# candle.net
KiCad netlist of a schematic drawn in EAGLE
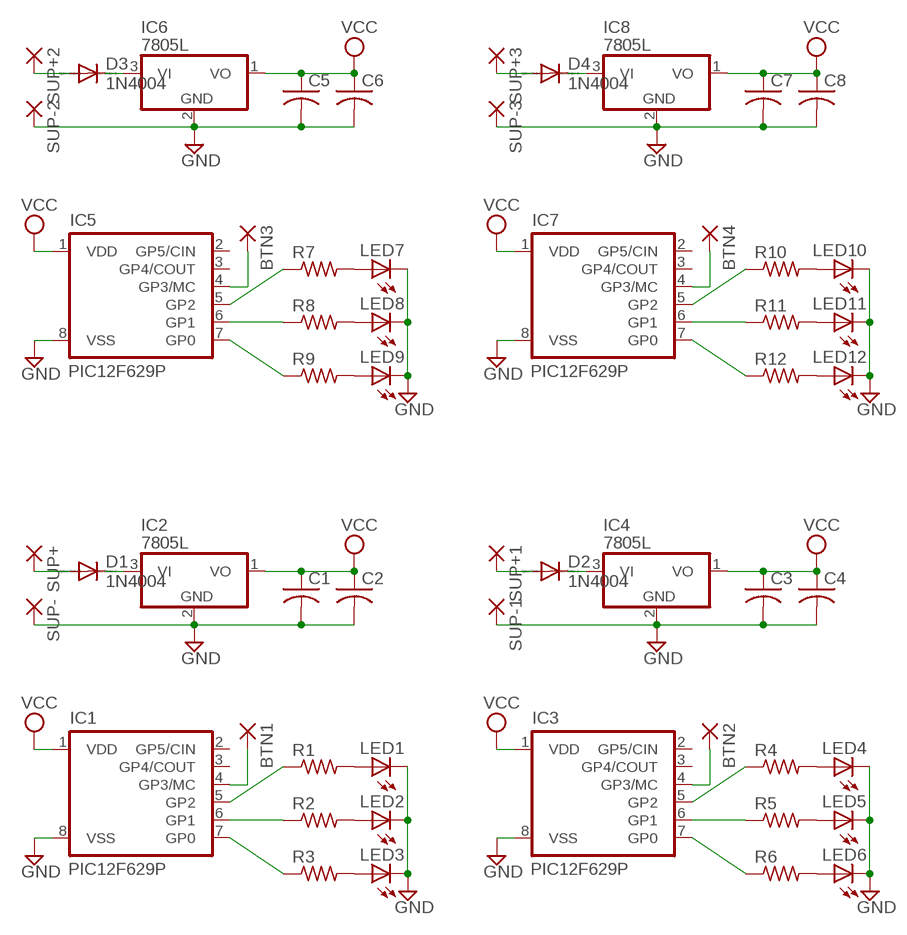
[diagram p0: schematic, sheet 1]

(export (version "E")
  (design (tool "Eeschema 10.0.6"))
  (components
    (comp (ref "BTN1")
      (value "1,6/0,8")
      (footprint "eagle-import:1,6_0,8")
      (libsource (lib "eagle-import") (part "1,6/0,8"))
    )
    (comp (ref "BTN2")
      (value "1,6/0,8")
      (footprint "eagle-import:1,6_0,8")
      (libsource (lib "eagle-import") (part "1,6/0,8"))
    )
    (comp (ref "BTN3")
      (value "1,6/0,8")
      (footprint "eagle-import:1,6_0,8")
      (libsource (lib "eagle-import") (part "1,6/0,8"))
    )
    (comp (ref "BTN4")
      (value "1,6/0,8")
      (footprint "eagle-import:1,6_0,8")
      (libsource (lib "eagle-import") (part "1,6/0,8"))
    )
    (comp (ref "C1")
      (value "C-US025-025X050")
      (footprint "eagle-import:C025-025X050")
      (libsource (lib "eagle-import") (part "C-US025-025X050"))
    )
    (comp (ref "C2")
      (value "C-US025-025X050")
      (footprint "eagle-import:C025-025X050")
      (libsource (lib "eagle-import") (part "C-US025-025X050"))
    )
    (comp (ref "C3")
      (value "C-US025-025X050")
      (footprint "eagle-import:C025-025X050")
      (libsource (lib "eagle-import") (part "C-US025-025X050"))
    )
    (comp (ref "C4")
      (value "C-US025-025X050")
      (footprint "eagle-import:C025-025X050")
      (libsource (lib "eagle-import") (part "C-US025-025X050"))
    )
    (comp (ref "C5")
      (value "C-US025-025X050")
      (footprint "eagle-import:C025-025X050")
      (libsource (lib "eagle-import") (part "C-US025-025X050"))
    )
    (comp (ref "C6")
      (value "C-US025-025X050")
      (footprint "eagle-import:C025-025X050")
      (libsource (lib "eagle-import") (part "C-US025-025X050"))
    )
    (comp (ref "C7")
      (value "C-US025-025X050")
      (footprint "eagle-import:C025-025X050")
      (libsource (lib "eagle-import") (part "C-US025-025X050"))
    )
    (comp (ref "C8")
      (value "C-US025-025X050")
      (footprint "eagle-import:C025-025X050")
      (libsource (lib "eagle-import") (part "C-US025-025X050"))
    )
    (comp (ref "D1")
      (value "1N4004")
      (footprint "eagle-import:DO41-10")
      (libsource (lib "eagle-import") (part "1N4004"))
    )
    (comp (ref "D2")
      (value "1N4004")
      (footprint "eagle-import:DO41-10")
      (libsource (lib "eagle-import") (part "1N4004"))
    )
    (comp (ref "D3")
      (value "1N4004")
      (footprint "eagle-import:DO41-10")
      (libsource (lib "eagle-import") (part "1N4004"))
    )
    (comp (ref "D4")
      (value "1N4004")
      (footprint "eagle-import:DO41-10")
      (libsource (lib "eagle-import") (part "1N4004"))
    )
    (comp (ref "IC1")
      (value "PIC12F629P")
      (footprint "eagle-import:DIL8")
      (fields (field (name "MF") "MICROCHIP") (field (name "MPN") "PIC12C671-10/P"))
      (libsource (lib "eagle-import") (part "PIC12C?P671"))
    )
    (comp (ref "IC2")
      (value "7805L")
      (footprint "eagle-import:TO92")
      (libsource (lib "eagle-import") (part "78L05"))
    )
    (comp (ref "IC3")
      (value "PIC12F629P")
      (footprint "eagle-import:DIL8")
      (fields (field (name "MF") "MICROCHIP") (field (name "MPN") "PIC12C671-10/P"))
      (libsource (lib "eagle-import") (part "PIC12C?P671"))
    )
    (comp (ref "IC4")
      (value "7805L")
      (footprint "eagle-import:TO92")
      (libsource (lib "eagle-import") (part "78L05"))
    )
    (comp (ref "IC5")
      (value "PIC12F629P")
      (footprint "eagle-import:DIL8")
      (fields (field (name "MF") "MICROCHIP") (field (name "MPN") "PIC12C671-10/P"))
      (libsource (lib "eagle-import") (part "PIC12C?P671"))
    )
    (comp (ref "IC6")
      (value "7805L")
      (footprint "eagle-import:TO92")
      (libsource (lib "eagle-import") (part "78L05"))
    )
    (comp (ref "IC7")
      (value "PIC12F629P")
      (footprint "eagle-import:DIL8")
      (fields (field (name "MF") "MICROCHIP") (field (name "MPN") "PIC12C671-10/P"))
      (libsource (lib "eagle-import") (part "PIC12C?P671"))
    )
    (comp (ref "IC8")
      (value "7805L")
      (footprint "eagle-import:TO92")
      (libsource (lib "eagle-import") (part "78L05"))
    )
    (comp (ref "LED1")
      (value "LED5MM")
      (footprint "eagle-import:LED5MM")
      (libsource (lib "eagle-import") (part "LED5MM"))
    )
    (comp (ref "LED2")
      (value "LED5MM")
      (footprint "eagle-import:LED5MM")
      (libsource (lib "eagle-import") (part "LED5MM"))
    )
    (comp (ref "LED3")
      (value "LED5MM")
      (footprint "eagle-import:LED5MM")
      (libsource (lib "eagle-import") (part "LED5MM"))
    )
    (comp (ref "LED4")
      (value "LED5MM")
      (footprint "eagle-import:LED5MM")
      (libsource (lib "eagle-import") (part "LED5MM"))
    )
    (comp (ref "LED5")
      (value "LED5MM")
      (footprint "eagle-import:LED5MM")
      (libsource (lib "eagle-import") (part "LED5MM"))
    )
    (comp (ref "LED6")
      (value "LED5MM")
      (footprint "eagle-import:LED5MM")
      (libsource (lib "eagle-import") (part "LED5MM"))
    )
    (comp (ref "LED7")
      (value "LED5MM")
      (footprint "eagle-import:LED5MM")
      (libsource (lib "eagle-import") (part "LED5MM"))
    )
    (comp (ref "LED8")
      (value "LED5MM")
      (footprint "eagle-import:LED5MM")
      (libsource (lib "eagle-import") (part "LED5MM"))
    )
    (comp (ref "LED9")
      (value "LED5MM")
      (footprint "eagle-import:LED5MM")
      (libsource (lib "eagle-import") (part "LED5MM"))
    )
    (comp (ref "LED10")
      (value "LED5MM")
      (footprint "eagle-import:LED5MM")
      (libsource (lib "eagle-import") (part "LED5MM"))
    )
    (comp (ref "LED11")
      (value "LED5MM")
      (footprint "eagle-import:LED5MM")
      (libsource (lib "eagle-import") (part "LED5MM"))
    )
    (comp (ref "LED12")
      (value "LED5MM")
      (footprint "eagle-import:LED5MM")
      (libsource (lib "eagle-import") (part "LED5MM"))
    )
    (comp (ref "R1")
      (value "R-US_0204/7")
      (footprint "eagle-import:0204_7")
      (libsource (lib "eagle-import") (part "R-US_0204/7"))
    )
    (comp (ref "R2")
      (value "R-US_0204/7")
      (footprint "eagle-import:0204_7")
      (libsource (lib "eagle-import") (part "R-US_0204/7"))
    )
    (comp (ref "R3")
      (value "R-US_0204/7")
      (footprint "eagle-import:0204_7")
      (libsource (lib "eagle-import") (part "R-US_0204/7"))
    )
    (comp (ref "R4")
      (value "R-US_0204/7")
      (footprint "eagle-import:0204_7")
      (libsource (lib "eagle-import") (part "R-US_0204/7"))
    )
    (comp (ref "R5")
      (value "R-US_0204/7")
      (footprint "eagle-import:0204_7")
      (libsource (lib "eagle-import") (part "R-US_0204/7"))
    )
    (comp (ref "R6")
      (value "R-US_0204/7")
      (footprint "eagle-import:0204_7")
      (libsource (lib "eagle-import") (part "R-US_0204/7"))
    )
    (comp (ref "R7")
      (value "R-US_0204/7")
      (footprint "eagle-import:0204_7")
      (libsource (lib "eagle-import") (part "R-US_0204/7"))
    )
    (comp (ref "R8")
      (value "R-US_0204/7")
      (footprint "eagle-import:0204_7")
      (libsource (lib "eagle-import") (part "R-US_0204/7"))
    )
    (comp (ref "R9")
      (value "R-US_0204/7")
      (footprint "eagle-import:0204_7")
      (libsource (lib "eagle-import") (part "R-US_0204/7"))
    )
    (comp (ref "R10")
      (value "R-US_0204/7")
      (footprint "eagle-import:0204_7")
      (libsource (lib "eagle-import") (part "R-US_0204/7"))
    )
    (comp (ref "R11")
      (value "R-US_0204/7")
      (footprint "eagle-import:0204_7")
      (libsource (lib "eagle-import") (part "R-US_0204/7"))
    )
    (comp (ref "R12")
      (value "R-US_0204/7")
      (footprint "eagle-import:0204_7")
      (libsource (lib "eagle-import") (part "R-US_0204/7"))
    )
    (comp (ref "SUP+")
      (value "1,6/0,8")
      (footprint "eagle-import:1,6_0,8")
      (libsource (lib "eagle-import") (part "1,6/0,8"))
    )
    (comp (ref "SUP+1")
      (value "1,6/0,8")
      (footprint "eagle-import:1,6_0,8")
      (libsource (lib "eagle-import") (part "1,6/0,8"))
    )
    (comp (ref "SUP+2")
      (value "1,6/0,8")
      (footprint "eagle-import:1,6_0,8")
      (libsource (lib "eagle-import") (part "1,6/0,8"))
    )
    (comp (ref "SUP+3")
      (value "1,6/0,8")
      (footprint "eagle-import:1,6_0,8")
      (libsource (lib "eagle-import") (part "1,6/0,8"))
    )
    (comp (ref "SUP-")
      (value "1,6/0,8")
      (footprint "eagle-import:1,6_0,8")
      (libsource (lib "eagle-import") (part "1,6/0,8"))
    )
    (comp (ref "SUP-1")
      (value "1,6/0,8")
      (footprint "eagle-import:1,6_0,8")
      (libsource (lib "eagle-import") (part "1,6/0,8"))
    )
    (comp (ref "SUP-2")
      (value "1,6/0,8")
      (footprint "eagle-import:1,6_0,8")
      (libsource (lib "eagle-import") (part "1,6/0,8"))
    )
    (comp (ref "SUP-3")
      (value "1,6/0,8")
      (footprint "eagle-import:1,6_0,8")
      (libsource (lib "eagle-import") (part "1,6/0,8"))
    )
  )
  (nets
    (net (code "1") (name "GND") (class "Default")
      (node (ref "C1") (pin "2") (pinfunction "2_2") (pintype "passive"))
      (node (ref "C2") (pin "2") (pinfunction "2_2") (pintype "passive"))
      (node (ref "C3") (pin "2") (pinfunction "2_2") (pintype "passive"))
      (node (ref "C4") (pin "2") (pinfunction "2_2") (pintype "passive"))
      (node (ref "C5") (pin "2") (pinfunction "2_2") (pintype "passive"))
      (node (ref "C6") (pin "2") (pinfunction "2_2") (pintype "passive"))
      (node (ref "C7") (pin "2") (pinfunction "2_2") (pintype "passive"))
      (node (ref "C8") (pin "2") (pinfunction "2_2") (pintype "passive"))
      (node (ref "IC1") (pin "8") (pinfunction "VSS_8") (pintype "power_in"))
      (node (ref "IC2") (pin "2") (pinfunction "GND_2") (pintype "passive"))
      (node (ref "IC3") (pin "8") (pinfunction "VSS_8") (pintype "power_in"))
      (node (ref "IC4") (pin "2") (pinfunction "GND_2") (pintype "passive"))
      (node (ref "IC5") (pin "8") (pinfunction "VSS_8") (pintype "power_in"))
      (node (ref "IC6") (pin "2") (pinfunction "GND_2") (pintype "passive"))
      (node (ref "IC7") (pin "8") (pinfunction "VSS_8") (pintype "power_in"))
      (node (ref "IC8") (pin "2") (pinfunction "GND_2") (pintype "passive"))
      (node (ref "LED1") (pin "K") (pinfunction "C_K") (pintype "passive"))
      (node (ref "LED10") (pin "K") (pinfunction "C_K") (pintype "passive"))
      (node (ref "LED11") (pin "K") (pinfunction "C_K") (pintype "passive"))
      (node (ref "LED12") (pin "K") (pinfunction "C_K") (pintype "passive"))
      (node (ref "LED2") (pin "K") (pinfunction "C_K") (pintype "passive"))
      (node (ref "LED3") (pin "K") (pinfunction "C_K") (pintype "passive"))
      (node (ref "LED4") (pin "K") (pinfunction "C_K") (pintype "passive"))
      (node (ref "LED5") (pin "K") (pinfunction "C_K") (pintype "passive"))
      (node (ref "LED6") (pin "K") (pinfunction "C_K") (pintype "passive"))
      (node (ref "LED7") (pin "K") (pinfunction "C_K") (pintype "passive"))
      (node (ref "LED8") (pin "K") (pinfunction "C_K") (pintype "passive"))
      (node (ref "LED9") (pin "K") (pinfunction "C_K") (pintype "passive"))
      (node (ref "SUP-") (pin "1") (pinfunction "P_1") (pintype "passive"))
      (node (ref "SUP-1") (pin "1") (pinfunction "P_1") (pintype "passive"))
      (node (ref "SUP-2") (pin "1") (pinfunction "P_1") (pintype "passive"))
      (node (ref "SUP-3") (pin "1") (pinfunction "P_1") (pintype "passive"))
    )
    (net (code "2") (name "Net-(BTN1-P)") (class "Default")
      (node (ref "BTN1") (pin "1") (pinfunction "P_1") (pintype "passive"))
      (node (ref "IC1") (pin "4") (pinfunction "GP3/MC_4") (pintype "input"))
    )
    (net (code "3") (name "Net-(BTN2-P)") (class "Default")
      (node (ref "BTN2") (pin "1") (pinfunction "P_1") (pintype "passive"))
      (node (ref "IC3") (pin "4") (pinfunction "GP3/MC_4") (pintype "input"))
    )
    (net (code "4") (name "Net-(BTN3-P)") (class "Default")
      (node (ref "BTN3") (pin "1") (pinfunction "P_1") (pintype "passive"))
      (node (ref "IC5") (pin "4") (pinfunction "GP3/MC_4") (pintype "input"))
    )
    (net (code "5") (name "Net-(BTN4-P)") (class "Default")
      (node (ref "BTN4") (pin "1") (pinfunction "P_1") (pintype "passive"))
      (node (ref "IC7") (pin "4") (pinfunction "GP3/MC_4") (pintype "input"))
    )
    (net (code "6") (name "Net-(IC1-GP0)") (class "Default")
      (node (ref "IC1") (pin "7") (pinfunction "GP0_7") (pintype "bidirectional"))
      (node (ref "R3") (pin "1") (pinfunction "1_1") (pintype "passive"))
    )
    (net (code "7") (name "Net-(IC1-GP1)") (class "Default")
      (node (ref "IC1") (pin "6") (pinfunction "GP1_6") (pintype "bidirectional"))
      (node (ref "R2") (pin "1") (pinfunction "1_1") (pintype "passive"))
    )
    (net (code "8") (name "Net-(IC1-GP2)") (class "Default")
      (node (ref "IC1") (pin "5") (pinfunction "GP2_5") (pintype "bidirectional"))
      (node (ref "R1") (pin "1") (pinfunction "1_1") (pintype "passive"))
    )
    (net (code "9") (name "Net-(IC2-VI)") (class "Default")
      (node (ref "D1") (pin "C") (pinfunction "C_C") (pintype "passive"))
      (node (ref "IC2") (pin "3") (pinfunction "VI_3") (pintype "input"))
    )
    (net (code "10") (name "Net-(IC3-GP0)") (class "Default")
      (node (ref "IC3") (pin "7") (pinfunction "GP0_7") (pintype "bidirectional"))
      (node (ref "R6") (pin "1") (pinfunction "1_1") (pintype "passive"))
    )
    (net (code "11") (name "Net-(IC3-GP1)") (class "Default")
      (node (ref "IC3") (pin "6") (pinfunction "GP1_6") (pintype "bidirectional"))
      (node (ref "R5") (pin "1") (pinfunction "1_1") (pintype "passive"))
    )
    (net (code "12") (name "Net-(IC3-GP2)") (class "Default")
      (node (ref "IC3") (pin "5") (pinfunction "GP2_5") (pintype "bidirectional"))
      (node (ref "R4") (pin "1") (pinfunction "1_1") (pintype "passive"))
    )
    (net (code "13") (name "Net-(IC4-VI)") (class "Default")
      (node (ref "D2") (pin "C") (pinfunction "C_C") (pintype "passive"))
      (node (ref "IC4") (pin "3") (pinfunction "VI_3") (pintype "input"))
    )
    (net (code "14") (name "Net-(IC5-GP0)") (class "Default")
      (node (ref "IC5") (pin "7") (pinfunction "GP0_7") (pintype "bidirectional"))
      (node (ref "R9") (pin "1") (pinfunction "1_1") (pintype "passive"))
    )
    (net (code "15") (name "Net-(IC5-GP1)") (class "Default")
      (node (ref "IC5") (pin "6") (pinfunction "GP1_6") (pintype "bidirectional"))
      (node (ref "R8") (pin "1") (pinfunction "1_1") (pintype "passive"))
    )
    (net (code "16") (name "Net-(IC5-GP2)") (class "Default")
      (node (ref "IC5") (pin "5") (pinfunction "GP2_5") (pintype "bidirectional"))
      (node (ref "R7") (pin "1") (pinfunction "1_1") (pintype "passive"))
    )
    (net (code "17") (name "Net-(IC6-VI)") (class "Default")
      (node (ref "D3") (pin "C") (pinfunction "C_C") (pintype "passive"))
      (node (ref "IC6") (pin "3") (pinfunction "VI_3") (pintype "input"))
    )
    (net (code "18") (name "Net-(IC7-GP0)") (class "Default")
      (node (ref "IC7") (pin "7") (pinfunction "GP0_7") (pintype "bidirectional"))
      (node (ref "R12") (pin "1") (pinfunction "1_1") (pintype "passive"))
    )
    (net (code "19") (name "Net-(IC7-GP1)") (class "Default")
      (node (ref "IC7") (pin "6") (pinfunction "GP1_6") (pintype "bidirectional"))
      (node (ref "R11") (pin "1") (pinfunction "1_1") (pintype "passive"))
    )
    (net (code "20") (name "Net-(IC7-GP2)") (class "Default")
      (node (ref "IC7") (pin "5") (pinfunction "GP2_5") (pintype "bidirectional"))
      (node (ref "R10") (pin "1") (pinfunction "1_1") (pintype "passive"))
    )
    (net (code "21") (name "Net-(IC8-VI)") (class "Default")
      (node (ref "D4") (pin "C") (pinfunction "C_C") (pintype "passive"))
      (node (ref "IC8") (pin "3") (pinfunction "VI_3") (pintype "input"))
    )
    (net (code "22") (name "Net-(LED1-PadA)") (class "Default")
      (node (ref "LED1") (pin "A") (pinfunction "A_A") (pintype "passive"))
      (node (ref "R1") (pin "2") (pinfunction "2_2") (pintype "passive"))
    )
    (net (code "23") (name "Net-(LED2-PadA)") (class "Default")
      (node (ref "LED2") (pin "A") (pinfunction "A_A") (pintype "passive"))
      (node (ref "R2") (pin "2") (pinfunction "2_2") (pintype "passive"))
    )
    (net (code "24") (name "Net-(LED3-PadA)") (class "Default")
      (node (ref "LED3") (pin "A") (pinfunction "A_A") (pintype "passive"))
      (node (ref "R3") (pin "2") (pinfunction "2_2") (pintype "passive"))
    )
    (net (code "25") (name "Net-(LED4-PadA)") (class "Default")
      (node (ref "LED4") (pin "A") (pinfunction "A_A") (pintype "passive"))
      (node (ref "R4") (pin "2") (pinfunction "2_2") (pintype "passive"))
    )
    (net (code "26") (name "Net-(LED5-PadA)") (class "Default")
      (node (ref "LED5") (pin "A") (pinfunction "A_A") (pintype "passive"))
      (node (ref "R5") (pin "2") (pinfunction "2_2") (pintype "passive"))
    )
    (net (code "27") (name "Net-(LED6-PadA)") (class "Default")
      (node (ref "LED6") (pin "A") (pinfunction "A_A") (pintype "passive"))
      (node (ref "R6") (pin "2") (pinfunction "2_2") (pintype "passive"))
    )
    (net (code "28") (name "Net-(LED7-PadA)") (class "Default")
      (node (ref "LED7") (pin "A") (pinfunction "A_A") (pintype "passive"))
      (node (ref "R7") (pin "2") (pinfunction "2_2") (pintype "passive"))
    )
    (net (code "29") (name "Net-(LED8-PadA)") (class "Default")
      (node (ref "LED8") (pin "A") (pinfunction "A_A") (pintype "passive"))
      (node (ref "R8") (pin "2") (pinfunction "2_2") (pintype "passive"))
    )
    (net (code "30") (name "Net-(LED9-PadA)") (class "Default")
      (node (ref "LED9") (pin "A") (pinfunction "A_A") (pintype "passive"))
      (node (ref "R9") (pin "2") (pinfunction "2_2") (pintype "passive"))
    )
    (net (code "31") (name "Net-(LED10-PadA)") (class "Default")
      (node (ref "LED10") (pin "A") (pinfunction "A_A") (pintype "passive"))
      (node (ref "R10") (pin "2") (pinfunction "2_2") (pintype "passive"))
    )
    (net (code "32") (name "Net-(LED11-PadA)") (class "Default")
      (node (ref "LED11") (pin "A") (pinfunction "A_A") (pintype "passive"))
      (node (ref "R11") (pin "2") (pinfunction "2_2") (pintype "passive"))
    )
    (net (code "33") (name "Net-(LED12-PadA)") (class "Default")
      (node (ref "LED12") (pin "A") (pinfunction "A_A") (pintype "passive"))
      (node (ref "R12") (pin "2") (pinfunction "2_2") (pintype "passive"))
    )
    (net (code "34") (name "Net-(SUP+-P)") (class "Default")
      (node (ref "D1") (pin "A") (pinfunction "A_A") (pintype "passive"))
      (node (ref "SUP+") (pin "1") (pinfunction "P_1") (pintype "passive"))
    )
    (net (code "35") (name "Net-(SUP+1-P)") (class "Default")
      (node (ref "D2") (pin "A") (pinfunction "A_A") (pintype "passive"))
      (node (ref "SUP+1") (pin "1") (pinfunction "P_1") (pintype "passive"))
    )
    (net (code "36") (name "Net-(SUP+2-P)") (class "Default")
      (node (ref "D3") (pin "A") (pinfunction "A_A") (pintype "passive"))
      (node (ref "SUP+2") (pin "1") (pinfunction "P_1") (pintype "passive"))
    )
    (net (code "37") (name "Net-(SUP+3-P)") (class "Default")
      (node (ref "D4") (pin "A") (pinfunction "A_A") (pintype "passive"))
      (node (ref "SUP+3") (pin "1") (pinfunction "P_1") (pintype "passive"))
    )
    (net (code "38") (name "VCC") (class "Default")
      (node (ref "C1") (pin "1") (pinfunction "1_1") (pintype "passive"))
      (node (ref "C2") (pin "1") (pinfunction "1_1") (pintype "passive"))
      (node (ref "C3") (pin "1") (pinfunction "1_1") (pintype "passive"))
      (node (ref "C4") (pin "1") (pinfunction "1_1") (pintype "passive"))
      (node (ref "C5") (pin "1") (pinfunction "1_1") (pintype "passive"))
      (node (ref "C6") (pin "1") (pinfunction "1_1") (pintype "passive"))
      (node (ref "C7") (pin "1") (pinfunction "1_1") (pintype "passive"))
      (node (ref "C8") (pin "1") (pinfunction "1_1") (pintype "passive"))
      (node (ref "IC1") (pin "1") (pinfunction "VDD_1") (pintype "power_in"))
      (node (ref "IC2") (pin "1") (pinfunction "VO_1") (pintype "passive"))
      (node (ref "IC3") (pin "1") (pinfunction "VDD_1") (pintype "power_in"))
      (node (ref "IC4") (pin "1") (pinfunction "VO_1") (pintype "passive"))
      (node (ref "IC5") (pin "1") (pinfunction "VDD_1") (pintype "power_in"))
      (node (ref "IC6") (pin "1") (pinfunction "VO_1") (pintype "passive"))
      (node (ref "IC7") (pin "1") (pinfunction "VDD_1") (pintype "power_in"))
      (node (ref "IC8") (pin "1") (pinfunction "VO_1") (pintype "passive"))
    )
    (net (code "39") (name "unconnected-(IC1-GP4{slash}COUT-Pad3)") (class "Default")
      (node (ref "IC1") (pin "3") (pinfunction "GP4/COUT_3") (pintype "bidirectional"))
    )
    (net (code "40") (name "unconnected-(IC1-GP5{slash}CIN-Pad2)") (class "Default")
      (node (ref "IC1") (pin "2") (pinfunction "GP5/CIN_2") (pintype "bidirectional"))
    )
    (net (code "41") (name "unconnected-(IC3-GP4{slash}COUT-Pad3)") (class "Default")
      (node (ref "IC3") (pin "3") (pinfunction "GP4/COUT_3") (pintype "bidirectional"))
    )
    (net (code "42") (name "unconnected-(IC3-GP5{slash}CIN-Pad2)") (class "Default")
      (node (ref "IC3") (pin "2") (pinfunction "GP5/CIN_2") (pintype "bidirectional"))
    )
    (net (code "43") (name "unconnected-(IC5-GP4{slash}COUT-Pad3)") (class "Default")
      (node (ref "IC5") (pin "3") (pinfunction "GP4/COUT_3") (pintype "bidirectional"))
    )
    (net (code "44") (name "unconnected-(IC5-GP5{slash}CIN-Pad2)") (class "Default")
      (node (ref "IC5") (pin "2") (pinfunction "GP5/CIN_2") (pintype "bidirectional"))
    )
    (net (code "45") (name "unconnected-(IC7-GP4{slash}COUT-Pad3)") (class "Default")
      (node (ref "IC7") (pin "3") (pinfunction "GP4/COUT_3") (pintype "bidirectional"))
    )
    (net (code "46") (name "unconnected-(IC7-GP5{slash}CIN-Pad2)") (class "Default")
      (node (ref "IC7") (pin "2") (pinfunction "GP5/CIN_2") (pintype "bidirectional"))
    )
  )
)
